# OSSI-1_Board_Riser.net
KiCad netlist of a schematic drawn in Altium Designer
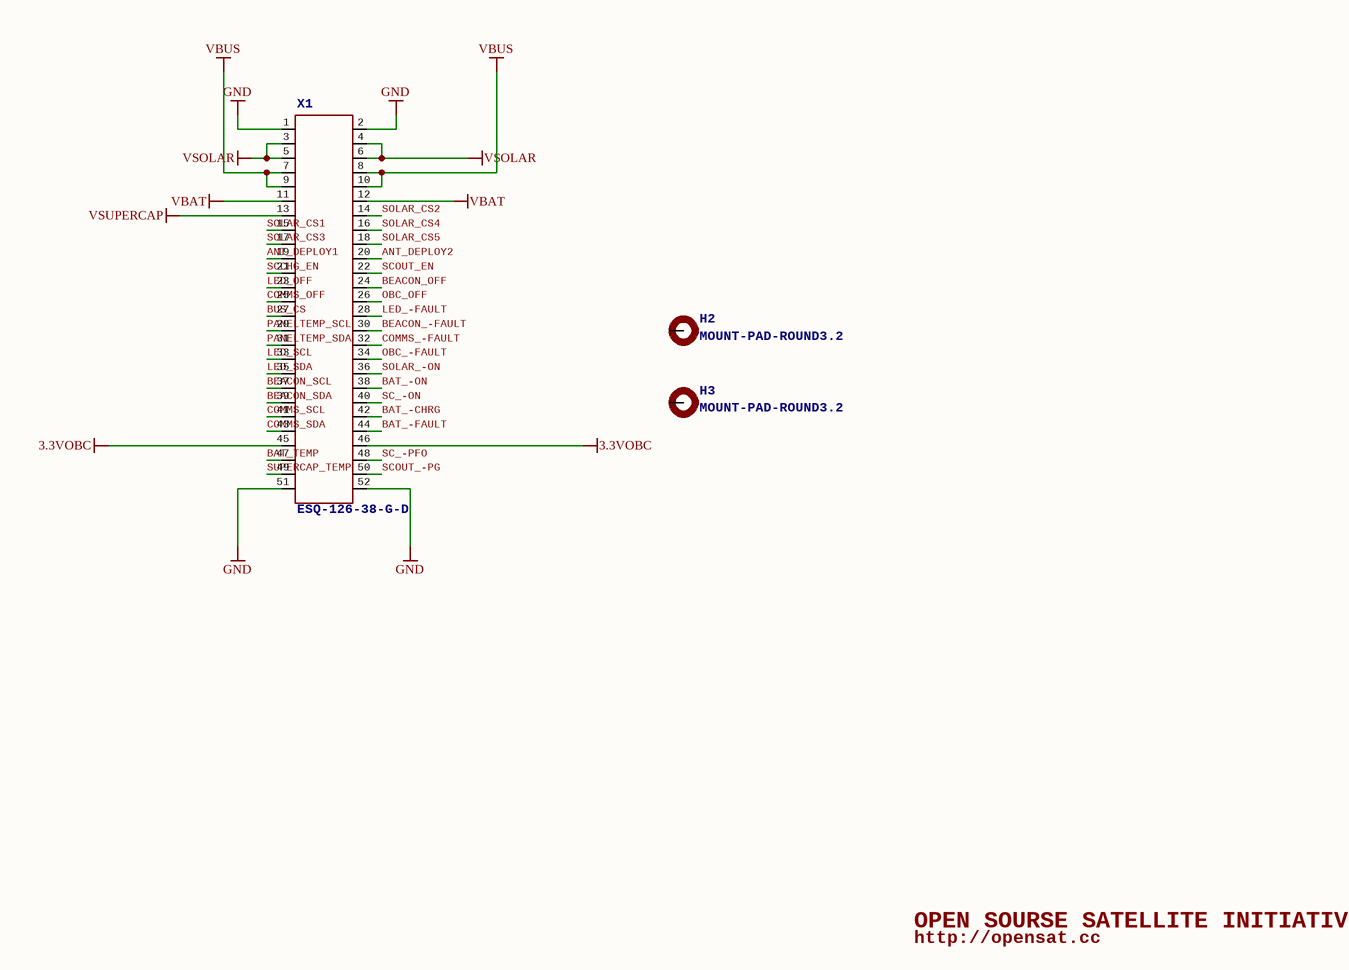
[diagram p0: OSSI-1 Board Riser.SchDoc]

(export (version "E")
  (design (tool "Eeschema 10.0.6"))
  (components
    (comp (ref "H2")
      (value "MOUNT-PAD-ROUND3.2")
      (footprint "3.2-PAD-ROUND")
      (fields (field (name ">NAME") "H2") (field (name ">VALUE") "MOUNT-PAD-ROUND3.2"))
      (libsource (lib "OSSI") (part "MOUNT-PAD-ROUND3.2"))
    )
    (comp (ref "H3")
      (value "MOUNT-PAD-ROUND3.2")
      (footprint "3.2-PAD-ROUND")
      (fields (field (name ">NAME") "H3") (field (name ">VALUE") "MOUNT-PAD-ROUND3.2"))
      (libsource (lib "OSSI") (part "MOUNT-PAD-ROUND3.2"))
    )
    (comp (ref "X1")
      (value "ESQ-126-38-G-D")
      (footprint "ESQ-126-XX-X-D")
      (fields (field (name ">NAME") "X1") (field (name ">VALUE") "ESQ-126-38-G-D"))
      (libsource (lib "OSSI") (part "ESQ-126-38-G-D"))
    )
  )
  (nets
    (net (code "1") (name "/ANT_DEPLOY1") (class "Default")
      (node (ref "X1") (pin "19") (pinfunction "19_19") (pintype "passive"))
    )
    (net (code "2") (name "/ANT_DEPLOY2") (class "Default")
      (node (ref "X1") (pin "20") (pinfunction "20_20") (pintype "passive"))
    )
    (net (code "3") (name "/BAT_-CHRG") (class "Default")
      (node (ref "X1") (pin "42") (pinfunction "42_42") (pintype "passive"))
    )
    (net (code "4") (name "/BAT_-FAULT") (class "Default")
      (node (ref "X1") (pin "44") (pinfunction "44_44") (pintype "passive"))
    )
    (net (code "5") (name "/BAT_-ON") (class "Default")
      (node (ref "X1") (pin "38") (pinfunction "38_38") (pintype "passive"))
    )
    (net (code "6") (name "/BAT_TEMP") (class "Default")
      (node (ref "X1") (pin "47") (pinfunction "47_47") (pintype "passive"))
    )
    (net (code "7") (name "/BEACON_-FAULT") (class "Default")
      (node (ref "X1") (pin "30") (pinfunction "30_30") (pintype "passive"))
    )
    (net (code "8") (name "/BEACON_OFF") (class "Default")
      (node (ref "X1") (pin "24") (pinfunction "24_24") (pintype "passive"))
    )
    (net (code "9") (name "/BEACON_SCL") (class "Default")
      (node (ref "X1") (pin "37") (pinfunction "37_37") (pintype "passive"))
    )
    (net (code "10") (name "/BEACON_SDA") (class "Default")
      (node (ref "X1") (pin "39") (pinfunction "39_39") (pintype "passive"))
    )
    (net (code "11") (name "/BUS_CS") (class "Default")
      (node (ref "X1") (pin "27") (pinfunction "27_27") (pintype "passive"))
    )
    (net (code "12") (name "/COMMS_-FAULT") (class "Default")
      (node (ref "X1") (pin "32") (pinfunction "32_32") (pintype "passive"))
    )
    (net (code "13") (name "/COMMS_OFF") (class "Default")
      (node (ref "X1") (pin "25") (pinfunction "25_25") (pintype "passive"))
    )
    (net (code "14") (name "/COMMS_SCL") (class "Default")
      (node (ref "X1") (pin "41") (pinfunction "41_41") (pintype "passive"))
    )
    (net (code "15") (name "/COMMS_SDA") (class "Default")
      (node (ref "X1") (pin "43") (pinfunction "43_43") (pintype "passive"))
    )
    (net (code "16") (name "/LED_-FAULT") (class "Default")
      (node (ref "X1") (pin "28") (pinfunction "28_28") (pintype "passive"))
    )
    (net (code "17") (name "/LED_OFF") (class "Default")
      (node (ref "X1") (pin "23") (pinfunction "23_23") (pintype "passive"))
    )
    (net (code "18") (name "/LED_SCL") (class "Default")
      (node (ref "X1") (pin "33") (pinfunction "33_33") (pintype "passive"))
    )
    (net (code "19") (name "/LED_SDA") (class "Default")
      (node (ref "X1") (pin "35") (pinfunction "35_35") (pintype "passive"))
    )
    (net (code "20") (name "/OBC_-FAULT") (class "Default")
      (node (ref "X1") (pin "34") (pinfunction "34_34") (pintype "passive"))
    )
    (net (code "21") (name "/OBC_OFF") (class "Default")
      (node (ref "X1") (pin "26") (pinfunction "26_26") (pintype "passive"))
    )
    (net (code "22") (name "/PANELTEMP_SCL") (class "Default")
      (node (ref "X1") (pin "29") (pinfunction "29_29") (pintype "passive"))
    )
    (net (code "23") (name "/PANELTEMP_SDA") (class "Default")
      (node (ref "X1") (pin "31") (pinfunction "31_31") (pintype "passive"))
    )
    (net (code "24") (name "/SCCHG_EN") (class "Default")
      (node (ref "X1") (pin "21") (pinfunction "21_21") (pintype "passive"))
    )
    (net (code "25") (name "/SCOUT_-PG") (class "Default")
      (node (ref "X1") (pin "50") (pinfunction "50_50") (pintype "passive"))
    )
    (net (code "26") (name "/SCOUT_EN") (class "Default")
      (node (ref "X1") (pin "22") (pinfunction "22_22") (pintype "passive"))
    )
    (net (code "27") (name "/SC_-ON") (class "Default")
      (node (ref "X1") (pin "40") (pinfunction "40_40") (pintype "passive"))
    )
    (net (code "28") (name "/SC_-PFO") (class "Default")
      (node (ref "X1") (pin "48") (pinfunction "48_48") (pintype "passive"))
    )
    (net (code "29") (name "/SOLAR_-ON") (class "Default")
      (node (ref "X1") (pin "36") (pinfunction "36_36") (pintype "passive"))
    )
    (net (code "30") (name "/SOLAR_CS1") (class "Default")
      (node (ref "X1") (pin "15") (pinfunction "15_15") (pintype "passive"))
    )
    (net (code "31") (name "/SOLAR_CS2") (class "Default")
      (node (ref "X1") (pin "14") (pinfunction "14_14") (pintype "passive"))
    )
    (net (code "32") (name "/SOLAR_CS3") (class "Default")
      (node (ref "X1") (pin "17") (pinfunction "17_17") (pintype "passive"))
    )
    (net (code "33") (name "/SOLAR_CS4") (class "Default")
      (node (ref "X1") (pin "16") (pinfunction "16_16") (pintype "passive"))
    )
    (net (code "34") (name "/SOLAR_CS5") (class "Default")
      (node (ref "X1") (pin "18") (pinfunction "18_18") (pintype "passive"))
    )
    (net (code "35") (name "/SUPERCAP_TEMP") (class "Default")
      (node (ref "X1") (pin "49") (pinfunction "49_49") (pintype "passive"))
    )
    (net (code "36") (name "3.3VOBC") (class "Default")
      (node (ref "X1") (pin "45") (pinfunction "45_45") (pintype "passive"))
      (node (ref "X1") (pin "46") (pinfunction "46_46") (pintype "passive"))
    )
    (net (code "37") (name "GND") (class "Default")
      (node (ref "X1") (pin "1") (pinfunction "1_1") (pintype "passive"))
      (node (ref "X1") (pin "2") (pinfunction "2_2") (pintype "passive"))
      (node (ref "X1") (pin "51") (pinfunction "51_51") (pintype "passive"))
      (node (ref "X1") (pin "52") (pinfunction "52_52") (pintype "passive"))
    )
    (net (code "38") (name "VBAT") (class "Default")
      (node (ref "X1") (pin "11") (pinfunction "11_11") (pintype "passive"))
      (node (ref "X1") (pin "12") (pinfunction "12_12") (pintype "passive"))
    )
    (net (code "39") (name "VBUS") (class "Default")
      (node (ref "X1") (pin "10") (pinfunction "10_10") (pintype "passive"))
      (node (ref "X1") (pin "7") (pinfunction "7_7") (pintype "passive"))
      (node (ref "X1") (pin "8") (pinfunction "8_8") (pintype "passive"))
      (node (ref "X1") (pin "9") (pinfunction "9_9") (pintype "passive"))
    )
    (net (code "40") (name "VSOLAR") (class "Default")
      (node (ref "X1") (pin "3") (pinfunction "3_3") (pintype "passive"))
      (node (ref "X1") (pin "4") (pinfunction "4_4") (pintype "passive"))
      (node (ref "X1") (pin "5") (pinfunction "5_5") (pintype "passive"))
      (node (ref "X1") (pin "6") (pinfunction "6_6") (pintype "passive"))
    )
    (net (code "41") (name "VSUPERCAP") (class "Default")
      (node (ref "X1") (pin "13") (pinfunction "13_13") (pintype "passive"))
    )
    (net (code "42") (name "unconnected-(H2-MOUNT-PadB3)") (class "Default")
      (node (ref "H2") (pin "B3") (pinfunction "MOUNT_B3") (pintype "passive"))
      (node (ref "H2") (pin "2") (pinfunction "MOUNT_2") (pintype "passive"))
    )
    (net (code "43") (name "unconnected-(H3-MOUNT-PadB3)") (class "Default")
      (node (ref "H3") (pin "B3") (pinfunction "MOUNT_B3") (pintype "passive"))
      (node (ref "H3") (pin "2") (pinfunction "MOUNT_2") (pintype "passive"))
    )
  )
)
